# DVD2.net
KiCad netlist of a schematic drawn in EAGLE
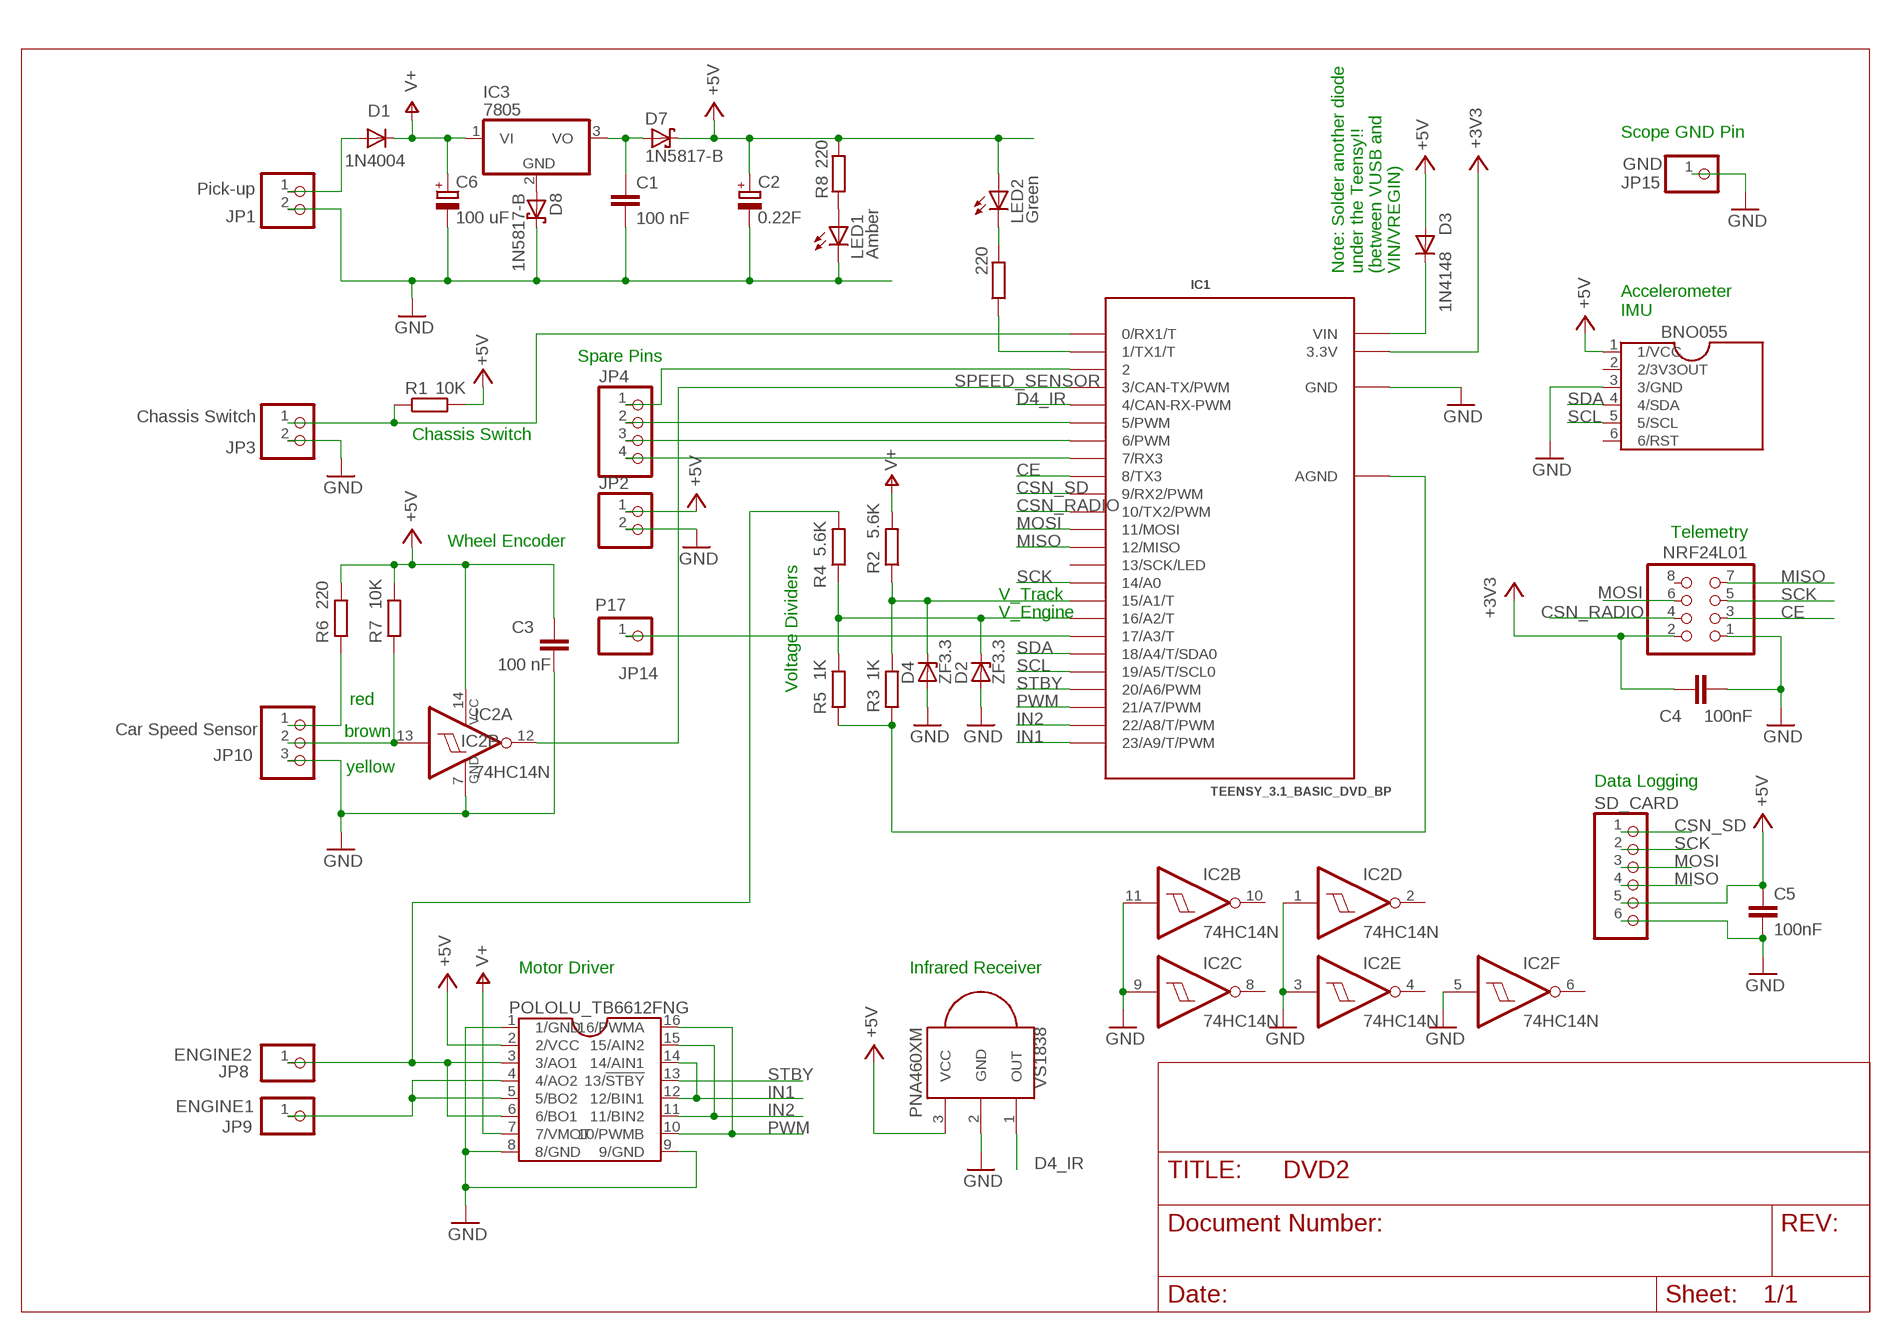
[diagram p0: schematic, sheet 1]

(export (version "E")
  (design (tool "Eeschema 10.0.6"))
  (components
    (comp (ref "BNO055")
      (value "BNO055_LIGHT")
      (footprint "eagle-import:DIL12-6-0")
      (libsource (lib "eagle-import") (part "BNO055_LIGHT"))
    )
    (comp (ref "C1")
      (value "100 nF")
      (footprint "eagle-import:C025-025X050")
      (libsource (lib "eagle-import") (part "resistor_C-EU025-025X050"))
    )
    (comp (ref "C2")
      (value "0.22F")
      (footprint "eagle-import:P128-50")
      (libsource (lib "eagle-import") (part "resistor_CPOL-EUP128-50"))
    )
    (comp (ref "C3")
      (value "100 nF")
      (footprint "eagle-import:C025-025X050")
      (libsource (lib "eagle-import") (part "resistor_C-EU025-025X050"))
    )
    (comp (ref "C4")
      (value "100nF")
      (footprint "eagle-import:C025-025X050")
      (libsource (lib "eagle-import") (part "resistor_C-EU025-025X050"))
    )
    (comp (ref "C5")
      (value "100nF")
      (footprint "eagle-import:C025-024X044")
      (libsource (lib "eagle-import") (part "C-EU025-024X044"))
    )
    (comp (ref "C6")
      (value "100 uF")
      (footprint "eagle-import:E2,5-6")
      (libsource (lib "eagle-import") (part "CPOL-EUE2.5-6"))
    )
    (comp (ref "D1")
      (value "1N4004")
      (footprint "eagle-import:DO41-10")
      (libsource (lib "eagle-import") (part "1N4004"))
    )
    (comp (ref "D2")
      (value "ZF3.3")
      (footprint "eagle-import:ZDIO-7.5")
      (libsource (lib "eagle-import") (part "ZENER-DIODEZD-7.5"))
    )
    (comp (ref "D3")
      (value "1N4148")
      (footprint "eagle-import:DO41-10")
      (libsource (lib "eagle-import") (part "1N4004"))
    )
    (comp (ref "D4")
      (value "ZF3.3")
      (footprint "eagle-import:ZDIO-7.5")
      (libsource (lib "eagle-import") (part "ZENER-DIODEZD-7.5"))
    )
    (comp (ref "D7")
      (value "1N5817-B")
      (footprint "eagle-import:DO41-7.6")
      (libsource (lib "eagle-import") (part "1N5817-B"))
    )
    (comp (ref "D8")
      (value "1N5817-B")
      (footprint "eagle-import:DO41-7.6")
      (libsource (lib "eagle-import") (part "1N5817-B"))
    )
    (comp (ref "IC1")
      (value "TEENSY_3.1_BASIC_DVD_BP")
      (footprint "eagle-import:TEENSY_3.1_BASIC_DVD_BIGPADS")
      (libsource (lib "eagle-import") (part "TEENSY_3.1_BASIC_DVD_BP"))
    )
    (comp (ref "IC2")
      (value "74HC14N")
      (footprint "eagle-import:DIL14")
      (libsource (lib "eagle-import") (part "7414NHC"))
    )
    (comp (ref "IC3")
      (value "7805")
      (footprint "eagle-import:TO220V")
      (libsource (lib "eagle-import") (part "78TV6"))
    )
    (comp (ref "IC4")
      (value "POLOLU_TB6612FNG")
      (footprint "eagle-import:DIL16WIDE")
      (libsource (lib "eagle-import") (part "POLOLU_TB6612FNG"))
    )
    (comp (ref "JP1")
      (value "Pick-up")
      (footprint "eagle-import:1X02")
      (libsource (lib "eagle-import") (part "PINHD-1X2"))
    )
    (comp (ref "JP2")
      (value "PINHD-1X2")
      (footprint "eagle-import:1X02")
      (libsource (lib "eagle-import") (part "PINHD-1X2"))
    )
    (comp (ref "JP3")
      (value "Chassis Switch")
      (footprint "eagle-import:1X02")
      (libsource (lib "eagle-import") (part "PINHD-1X2"))
    )
    (comp (ref "JP4")
      (value "PINHD-1X4")
      (footprint "eagle-import:1X04")
      (libsource (lib "eagle-import") (part "PINHD-1X4"))
    )
    (comp (ref "JP8")
      (value "ENGINE2")
      (footprint "eagle-import:1X01")
      (libsource (lib "eagle-import") (part "PINHD-1X1"))
    )
    (comp (ref "JP9")
      (value "ENGINE1")
      (footprint "eagle-import:1X01")
      (libsource (lib "eagle-import") (part "PINHD-1X1"))
    )
    (comp (ref "JP10")
      (value "Car Speed Sensor")
      (footprint "eagle-import:1X03")
      (libsource (lib "eagle-import") (part "PINHD-1X3"))
    )
    (comp (ref "JP14")
      (value "P17")
      (footprint "eagle-import:1X01")
      (libsource (lib "eagle-import") (part "PINHD-1X1"))
    )
    (comp (ref "JP15")
      (value "GND")
      (footprint "eagle-import:1X01")
      (libsource (lib "eagle-import") (part "PINHD-1X1"))
    )
    (comp (ref "LED1")
      (value "Amber")
      (footprint "eagle-import:LED3MM")
      (libsource (lib "eagle-import") (part "LED3MM"))
    )
    (comp (ref "LED2")
      (value "Green")
      (footprint "eagle-import:LED3MM")
      (libsource (lib "eagle-import") (part "LED3MM"))
    )
    (comp (ref "NRF24L01")
      (value "PINHD-2X4")
      (footprint "eagle-import:2X04")
      (libsource (lib "eagle-import") (part "PINHD-2X4"))
    )
    (comp (ref "R1")
      (value "10K")
      (footprint "eagle-import:0207_10")
      (libsource (lib "eagle-import") (part "R-EU_0207/10"))
    )
    (comp (ref "R2")
      (value "5.6K")
      (footprint "eagle-import:0207_10")
      (libsource (lib "eagle-import") (part "R-EU_0207/10"))
    )
    (comp (ref "R3")
      (value "1K")
      (footprint "eagle-import:0207_10")
      (libsource (lib "eagle-import") (part "R-EU_0207/10"))
    )
    (comp (ref "R4")
      (value "5.6K")
      (footprint "eagle-import:0207_10")
      (libsource (lib "eagle-import") (part "R-EU_0207/10"))
    )
    (comp (ref "R5")
      (value "1K")
      (footprint "eagle-import:0207_10")
      (libsource (lib "eagle-import") (part "R-EU_0207/10"))
    )
    (comp (ref "R6")
      (value "220")
      (footprint "eagle-import:0207_10")
      (libsource (lib "eagle-import") (part "R-EU_0207/10"))
    )
    (comp (ref "R7")
      (value "10K")
      (footprint "eagle-import:0207_10")
      (libsource (lib "eagle-import") (part "R-EU_0207/10"))
    )
    (comp (ref "R8")
      (value "220")
      (footprint "eagle-import:0207_10")
      (libsource (lib "eagle-import") (part "R-EU_0207/10"))
    )
    (comp (ref "R9")
      (value "220")
      (footprint "eagle-import:0207_10")
      (libsource (lib "eagle-import") (part "R-EU_0207/10"))
    )
    (comp (ref "SD_CARD")
      (value "PINHD-1X6")
      (footprint "eagle-import:1X06")
      (libsource (lib "eagle-import") (part "PINHD-1X6"))
    )
    (comp (ref "VS1838")
      (value "PNA460XM")
      (footprint "eagle-import:PNA460XM")
      (libsource (lib "eagle-import") (part "PNA460XM"))
    )
  )
  (nets
    (net (code "1") (name "+3V3") (class "Default")
      (node (ref "C4") (pin "1") (pinfunction "1_1") (pintype "passive"))
      (node (ref "IC1") (pin "3.3V") (pinfunction "3.3V_3.3V") (pintype "power_in"))
      (node (ref "NRF24L01") (pin "2") (pinfunction "2_2") (pintype "passive"))
    )
    (net (code "2") (name "+5V") (class "Default")
      (node (ref "BNO055") (pin "1") (pinfunction "1/VCC_1") (pintype "power_in"))
      (node (ref "C2") (pin "+") (pinfunction "+_+") (pintype "passive"))
      (node (ref "C3") (pin "1") (pinfunction "1_1") (pintype "passive"))
      (node (ref "C5") (pin "1") (pinfunction "1_1") (pintype "passive"))
      (node (ref "D3") (pin "A") (pinfunction "A_A") (pintype "passive"))
      (node (ref "D7") (pin "C") (pinfunction "C_C") (pintype "passive"))
      (node (ref "IC2") (pin "14") (pinfunction "VCC_14") (pintype "power_in"))
      (node (ref "IC4") (pin "2") (pinfunction "2/VCC_2") (pintype "power_in"))
      (node (ref "JP2") (pin "1") (pinfunction "1_1") (pintype "passive"))
      (node (ref "LED2") (pin "A") (pinfunction "A_A") (pintype "passive"))
      (node (ref "R1") (pin "2") (pinfunction "2_2") (pintype "passive"))
      (node (ref "R6") (pin "2") (pinfunction "2_2") (pintype "passive"))
      (node (ref "R7") (pin "2") (pinfunction "2_2") (pintype "passive"))
      (node (ref "R8") (pin "2") (pinfunction "2_2") (pintype "passive"))
      (node (ref "SD_CARD") (pin "5") (pinfunction "5_5") (pintype "passive"))
      (node (ref "VS1838") (pin "3") (pinfunction "VCC_3") (pintype "power_in"))
    )
    (net (code "3") (name "/2{slash}3V3OUT") (class "Default")
      (node (ref "BNO055") (pin "2") (pinfunction "2/3V3OUT_2") (pintype "power_in"))
    )
    (net (code "4") (name "/CE") (class "Default")
      (node (ref "IC1") (pin "8") (pinfunction "8/TX3_8") (pintype "bidirectional"))
      (node (ref "NRF24L01") (pin "3") (pinfunction "3_3") (pintype "passive"))
    )
    (net (code "5") (name "/CSN_RADIO") (class "Default")
      (node (ref "IC1") (pin "10") (pinfunction "10/TX2/PWM_10") (pintype "bidirectional"))
      (node (ref "NRF24L01") (pin "4") (pinfunction "4_4") (pintype "passive"))
    )
    (net (code "6") (name "/CSN_SD") (class "Default")
      (node (ref "IC1") (pin "9") (pinfunction "9/RX2/PWM_9") (pintype "bidirectional"))
      (node (ref "SD_CARD") (pin "1") (pinfunction "1_1") (pintype "passive"))
    )
    (net (code "7") (name "/D4_IR") (class "Default")
      (node (ref "IC1") (pin "4") (pinfunction "4/CAN-RX-PWM_4") (pintype "bidirectional"))
      (node (ref "VS1838") (pin "1") (pinfunction "OUT_1") (pintype "output"))
    )
    (net (code "8") (name "/IN1") (class "Default")
      (node (ref "IC1") (pin "23/A9") (pinfunction "23/A9/T/PWM_23/A9") (pintype "bidirectional"))
      (node (ref "IC4") (pin "12") (pinfunction "12/BIN1_12") (pintype "bidirectional"))
      (node (ref "IC4") (pin "14") (pinfunction "14/AIN1_14") (pintype "bidirectional"))
    )
    (net (code "9") (name "/IN2") (class "Default")
      (node (ref "IC1") (pin "22/A8") (pinfunction "22/A8/T/PWM_22/A8") (pintype "bidirectional"))
      (node (ref "IC4") (pin "11") (pinfunction "11/BIN2_11") (pintype "bidirectional"))
      (node (ref "IC4") (pin "15") (pinfunction "15/AIN2_15") (pintype "bidirectional"))
    )
    (net (code "10") (name "/MISO") (class "Default")
      (node (ref "IC1") (pin "12") (pinfunction "12/MISO_12") (pintype "bidirectional"))
      (node (ref "NRF24L01") (pin "7") (pinfunction "7_7") (pintype "passive"))
      (node (ref "SD_CARD") (pin "4") (pinfunction "4_4") (pintype "passive"))
    )
    (net (code "11") (name "/MOSI") (class "Default")
      (node (ref "IC1") (pin "11") (pinfunction "11/MOSI_11") (pintype "bidirectional"))
      (node (ref "NRF24L01") (pin "6") (pinfunction "6_6") (pintype "passive"))
      (node (ref "SD_CARD") (pin "3") (pinfunction "3_3") (pintype "passive"))
    )
    (net (code "12") (name "/PWM") (class "Default")
      (node (ref "IC1") (pin "21/A7") (pinfunction "21/A7/PWM_21/A7") (pintype "bidirectional"))
      (node (ref "IC4") (pin "10") (pinfunction "10/PWMB_10") (pintype "input"))
      (node (ref "IC4") (pin "16") (pinfunction "16/PWMA_16") (pintype "input"))
    )
    (net (code "13") (name "/SCK") (class "Default")
      (node (ref "IC1") (pin "14/A0") (pinfunction "14/A0_14/A0") (pintype "bidirectional"))
      (node (ref "NRF24L01") (pin "5") (pinfunction "5_5") (pintype "passive"))
      (node (ref "SD_CARD") (pin "2") (pinfunction "2_2") (pintype "passive"))
    )
    (net (code "14") (name "/SCL") (class "Default")
      (node (ref "BNO055") (pin "5") (pinfunction "5/SCL_5") (pintype "bidirectional"))
      (node (ref "IC1") (pin "19/A5") (pinfunction "19/A5/T/SCL0_19/A5") (pintype "bidirectional"))
    )
    (net (code "15") (name "/SDA") (class "Default")
      (node (ref "BNO055") (pin "4") (pinfunction "4/SDA_4") (pintype "bidirectional"))
      (node (ref "IC1") (pin "18/A4") (pinfunction "18/A4/T/SDA0_18/A4") (pintype "bidirectional"))
    )
    (net (code "16") (name "/SPEED_SENSOR") (class "Default")
      (node (ref "IC1") (pin "3") (pinfunction "3/CAN-TX/PWM_3") (pintype "bidirectional"))
      (node (ref "IC2") (pin "12") (pinfunction "O_12") (pintype "output"))
    )
    (net (code "17") (name "/STBY") (class "Default")
      (node (ref "IC1") (pin "20/A6") (pinfunction "20/A6/PWM_20/A6") (pintype "bidirectional"))
      (node (ref "IC4") (pin "13") (pinfunction "13/~{STBY}_13") (pintype "input"))
    )
    (net (code "18") (name "GND") (class "Default")
      (node (ref "BNO055") (pin "3") (pinfunction "3/GND_3") (pintype "power_in"))
      (node (ref "C1") (pin "2") (pinfunction "2_2") (pintype "passive"))
      (node (ref "C2") (pin "-") (pinfunction "-_-") (pintype "passive"))
      (node (ref "C3") (pin "2") (pinfunction "2_2") (pintype "passive"))
      (node (ref "C4") (pin "2") (pinfunction "2_2") (pintype "passive"))
      (node (ref "C5") (pin "2") (pinfunction "2_2") (pintype "passive"))
      (node (ref "C6") (pin "-") (pinfunction "-_-") (pintype "passive"))
      (node (ref "D2") (pin "A") (pinfunction "A_A") (pintype "passive"))
      (node (ref "D4") (pin "A") (pinfunction "A_A") (pintype "passive"))
      (node (ref "D8") (pin "C") (pinfunction "C_C") (pintype "passive"))
      (node (ref "IC1") (pin "GND") (pinfunction "GND_GND") (pintype "power_in"))
      (node (ref "IC2") (pin "1") (pinfunction "I_1") (pintype "input"))
      (node (ref "IC2") (pin "11") (pinfunction "I_11") (pintype "input"))
      (node (ref "IC2") (pin "3") (pinfunction "I_3") (pintype "input"))
      (node (ref "IC2") (pin "5") (pinfunction "I_5") (pintype "input"))
      (node (ref "IC2") (pin "7") (pinfunction "GND_7") (pintype "power_in"))
      (node (ref "IC2") (pin "9") (pinfunction "I_9") (pintype "input"))
      (node (ref "IC4") (pin "1") (pinfunction "1/GND_1") (pintype "power_in"))
      (node (ref "IC4") (pin "8") (pinfunction "8/GND_8") (pintype "power_in"))
      (node (ref "IC4") (pin "9") (pinfunction "9/GND_9") (pintype "power_in"))
      (node (ref "JP1") (pin "2") (pinfunction "2_2") (pintype "passive"))
      (node (ref "JP10") (pin "3") (pinfunction "3_3") (pintype "passive"))
      (node (ref "JP15") (pin "1") (pinfunction "1_1") (pintype "passive"))
      (node (ref "JP2") (pin "2") (pinfunction "2_2") (pintype "passive"))
      (node (ref "JP3") (pin "2") (pinfunction "2_2") (pintype "passive"))
      (node (ref "LED1") (pin "K") (pinfunction "C_K") (pintype "passive"))
      (node (ref "NRF24L01") (pin "1") (pinfunction "1_1") (pintype "passive"))
      (node (ref "SD_CARD") (pin "6") (pinfunction "6_6") (pintype "passive"))
      (node (ref "VS1838") (pin "2") (pinfunction "GND_2") (pintype "power_in"))
    )
    (net (code "19") (name "Net-(D1-PadA)") (class "Default")
      (node (ref "D1") (pin "A") (pinfunction "A_A") (pintype "passive"))
      (node (ref "JP1") (pin "1") (pinfunction "1_1") (pintype "passive"))
    )
    (net (code "20") (name "Net-(D3-PadC)") (class "Default")
      (node (ref "D3") (pin "C") (pinfunction "C_C") (pintype "passive"))
      (node (ref "IC1") (pin "VIN") (pinfunction "VIN_VIN") (pintype "power_in"))
    )
    (net (code "21") (name "Net-(IC1-0{slash}RX1{slash}T)") (class "Default")
      (node (ref "IC1") (pin "0") (pinfunction "0/RX1/T_0") (pintype "bidirectional"))
      (node (ref "JP3") (pin "1") (pinfunction "1_1") (pintype "passive"))
      (node (ref "R1") (pin "1") (pinfunction "1_1") (pintype "passive"))
    )
    (net (code "22") (name "Net-(IC1-1{slash}TX1{slash}T)") (class "Default")
      (node (ref "IC1") (pin "1") (pinfunction "1/TX1/T_1") (pintype "bidirectional"))
      (node (ref "R9") (pin "1") (pinfunction "1_1") (pintype "passive"))
    )
    (net (code "23") (name "Net-(IC1-5{slash}PWM)") (class "Default")
      (node (ref "IC1") (pin "5") (pinfunction "5/PWM_5") (pintype "bidirectional"))
      (node (ref "JP4") (pin "2") (pinfunction "2_2") (pintype "passive"))
    )
    (net (code "24") (name "Net-(IC1-6{slash}PWM)") (class "Default")
      (node (ref "IC1") (pin "6") (pinfunction "6/PWM_6") (pintype "bidirectional"))
      (node (ref "JP4") (pin "3") (pinfunction "3_3") (pintype "passive"))
    )
    (net (code "25") (name "Net-(IC1-7{slash}RX3)") (class "Default")
      (node (ref "IC1") (pin "7") (pinfunction "7/RX3_7") (pintype "bidirectional"))
      (node (ref "JP4") (pin "4") (pinfunction "4_4") (pintype "passive"))
    )
    (net (code "26") (name "Net-(IC1-15{slash}A1{slash}T)") (class "Default")
      (node (ref "D4") (pin "C") (pinfunction "C_C") (pintype "passive"))
      (node (ref "IC1") (pin "15/A1") (pinfunction "15/A1/T_15/A1") (pintype "bidirectional"))
      (node (ref "R2") (pin "1") (pinfunction "1_1") (pintype "passive"))
      (node (ref "R3") (pin "2") (pinfunction "2_2") (pintype "passive"))
    )
    (net (code "27") (name "Net-(IC1-16{slash}A2{slash}T)") (class "Default")
      (node (ref "D2") (pin "C") (pinfunction "C_C") (pintype "passive"))
      (node (ref "IC1") (pin "16/A2") (pinfunction "16/A2/T_16/A2") (pintype "bidirectional"))
      (node (ref "R4") (pin "1") (pinfunction "1_1") (pintype "passive"))
      (node (ref "R5") (pin "2") (pinfunction "2_2") (pintype "passive"))
    )
    (net (code "28") (name "Net-(IC1-17{slash}A3{slash}T)") (class "Default")
      (node (ref "IC1") (pin "17/A3") (pinfunction "17/A3/T_17/A3") (pintype "bidirectional"))
      (node (ref "JP14") (pin "1") (pinfunction "1_1") (pintype "passive"))
    )
    (net (code "29") (name "Net-(IC1-Pad2)") (class "Default")
      (node (ref "IC1") (pin "2") (pinfunction "2_2") (pintype "bidirectional"))
      (node (ref "JP4") (pin "1") (pinfunction "1_1") (pintype "passive"))
    )
    (net (code "30") (name "Net-(IC1-PadAGND)") (class "Default")
      (node (ref "IC1") (pin "AGND") (pinfunction "AGND_AGND") (pintype "power_in"))
      (node (ref "R3") (pin "1") (pinfunction "1_1") (pintype "passive"))
      (node (ref "R5") (pin "1") (pinfunction "1_1") (pintype "passive"))
    )
    (net (code "31") (name "Net-(IC2A-I)") (class "Default")
      (node (ref "IC2") (pin "13") (pinfunction "I_13") (pintype "input"))
      (node (ref "JP10") (pin "2") (pinfunction "2_2") (pintype "passive"))
      (node (ref "R7") (pin "1") (pinfunction "1_1") (pintype "passive"))
    )
    (net (code "32") (name "Net-(IC3-GND)") (class "Default")
      (node (ref "D8") (pin "A") (pinfunction "A_A") (pintype "passive"))
      (node (ref "IC3") (pin "2") (pinfunction "GND_2") (pintype "passive"))
    )
    (net (code "33") (name "Net-(IC3-VO)") (class "Default")
      (node (ref "C1") (pin "1") (pinfunction "1_1") (pintype "passive"))
      (node (ref "D7") (pin "A") (pinfunction "A_A") (pintype "passive"))
      (node (ref "IC3") (pin "3") (pinfunction "VO_3") (pintype "passive"))
    )
    (net (code "34") (name "Net-(IC4-3{slash}AO1)") (class "Default")
      (node (ref "IC4") (pin "3") (pinfunction "3/AO1_3") (pintype "bidirectional"))
      (node (ref "IC4") (pin "6") (pinfunction "6/BO1_6") (pintype "bidirectional"))
      (node (ref "JP8") (pin "1") (pinfunction "1_1") (pintype "passive"))
      (node (ref "R4") (pin "2") (pinfunction "2_2") (pintype "passive"))
    )
    (net (code "35") (name "Net-(IC4-4{slash}AO2)") (class "Default")
      (node (ref "IC4") (pin "4") (pinfunction "4/AO2_4") (pintype "bidirectional"))
      (node (ref "IC4") (pin "5") (pinfunction "5/BO2_5") (pintype "bidirectional"))
      (node (ref "JP9") (pin "1") (pinfunction "1_1") (pintype "passive"))
    )
    (net (code "36") (name "Net-(JP10-Pad1)") (class "Default")
      (node (ref "JP10") (pin "1") (pinfunction "1_1") (pintype "passive"))
      (node (ref "R6") (pin "1") (pinfunction "1_1") (pintype "passive"))
    )
    (net (code "37") (name "Net-(LED1-PadA)") (class "Default")
      (node (ref "LED1") (pin "A") (pinfunction "A_A") (pintype "passive"))
      (node (ref "R8") (pin "1") (pinfunction "1_1") (pintype "passive"))
    )
    (net (code "38") (name "Net-(LED2-C)") (class "Default")
      (node (ref "LED2") (pin "K") (pinfunction "C_K") (pintype "passive"))
      (node (ref "R9") (pin "2") (pinfunction "2_2") (pintype "passive"))
    )
    (net (code "39") (name "V+") (class "Default")
      (node (ref "C6") (pin "+") (pinfunction "+_+") (pintype "passive"))
      (node (ref "D1") (pin "C") (pinfunction "C_C") (pintype "passive"))
      (node (ref "IC3") (pin "1") (pinfunction "VI_1") (pintype "input"))
      (node (ref "IC4") (pin "7") (pinfunction "7/VMOT_7") (pintype "power_in"))
      (node (ref "R2") (pin "2") (pinfunction "2_2") (pintype "passive"))
    )
    (net (code "40") (name "unconnected-(BNO055-6{slash}RST-Pad6)") (class "Default")
      (node (ref "BNO055") (pin "6") (pinfunction "6/RST_6") (pintype "input"))
    )
    (net (code "41") (name "unconnected-(IC1-13{slash}SCK{slash}LED-Pad13)") (class "Default")
      (node (ref "IC1") (pin "13") (pinfunction "13/SCK/LED_13") (pintype "bidirectional"))
    )
    (net (code "42") (name "unconnected-(IC2B-O-Pad10)") (class "Default")
      (node (ref "IC2") (pin "10") (pinfunction "O_10") (pintype "output"))
    )
    (net (code "43") (name "unconnected-(IC2C-O-Pad8)") (class "Default")
      (node (ref "IC2") (pin "8") (pinfunction "O_8") (pintype "output"))
    )
    (net (code "44") (name "unconnected-(IC2D-O-Pad2)") (class "Default")
      (node (ref "IC2") (pin "2") (pinfunction "O_2") (pintype "output"))
    )
    (net (code "45") (name "unconnected-(IC2E-O-Pad4)") (class "Default")
      (node (ref "IC2") (pin "4") (pinfunction "O_4") (pintype "output"))
    )
    (net (code "46") (name "unconnected-(IC2F-O-Pad6)") (class "Default")
      (node (ref "IC2") (pin "6") (pinfunction "O_6") (pintype "output"))
    )
    (net (code "47") (name "unconnected-(NRF24L01-Pad8)") (class "Default")
      (node (ref "NRF24L01") (pin "8") (pinfunction "8_8") (pintype "passive"))
    )
  )
)
